# CON_SD_KSDC012551.net
KiCad netlist of a schematic drawn in Altium Designer
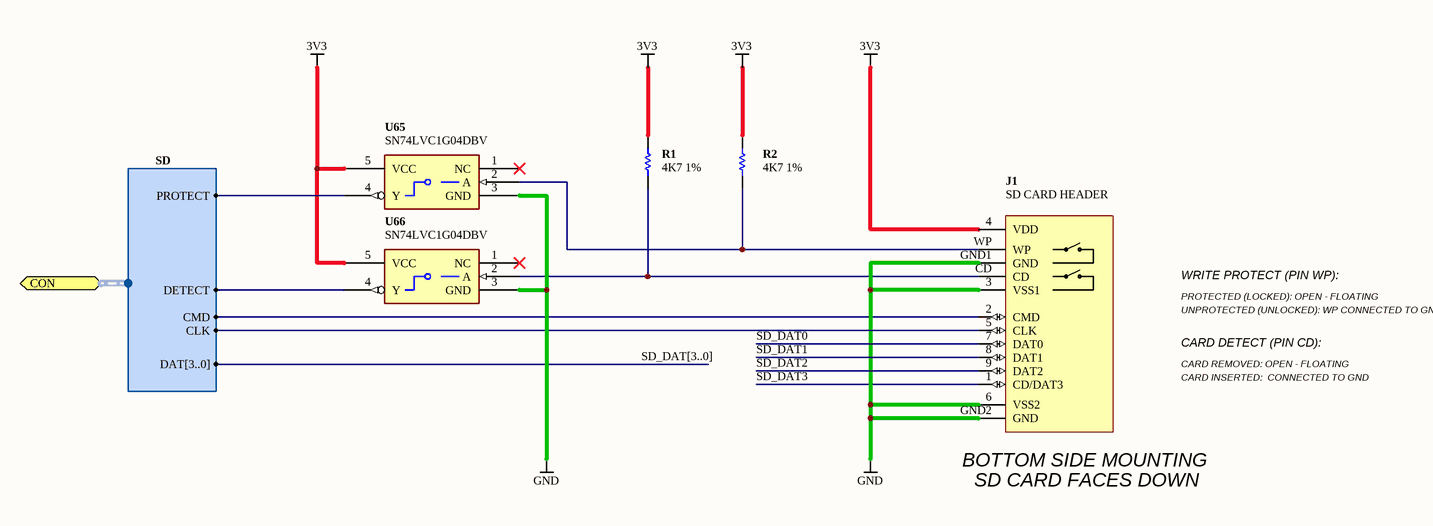
[diagram p0: CON_SD_KSDC012551.SchDoc]

(export (version "E")
  (design (tool "Eeschema 10.0.6"))
  (components
    (comp (ref "J1")
      (value "SD CARD HEADER")
      (footprint "KSDC012551")
      (description "Secure Digital Card Socket")
      (libsource (lib "AltiumDesignLibrary") (part "KSDC012551-9"))
    )
    (comp (ref "R1")
      (value "4K7 1%")
      (footprint "RESC1005-STAR")
      (description "Resistor, 4K7 1% 0402 (1005)")
      (fields (field (name "TOLERANCE") "1 %"))
      (libsource (lib "altium-import") (part "root_0_RES_"))
    )
    (comp (ref "R2")
      (value "4K7 1%")
      (footprint "RESC1005-STAR")
      (description "Resistor, 4K7 1% 0402 (1005)")
      (fields (field (name "TOLERANCE") "1 %"))
      (libsource (lib "altium-import") (part "root_0_RES_"))
    )
    (comp (ref "U65")
      (value "SN74LVC1G04DBV")
      (footprint "SOT95P280-5")
      (description "SN74LVC1G04DBV, Single Inverter Gate, 1.65-V to 5.5-V")
      (libsource (lib "AltiumDesignLibrary") (part "SN74LVC1G04DBV"))
    )
    (comp (ref "U66")
      (value "SN74LVC1G04DBV")
      (footprint "SOT95P280-5")
      (description "SN74LVC1G04DBV, Single Inverter Gate, 1.65-V to 5.5-V")
      (libsource (lib "AltiumDesignLibrary") (part "SN74LVC1G04DBV"))
    )
  )
  (nets
    (net (code "2") (name "/CLK") (class "Default")
      (node (ref "J1") (pin "5") (pinfunction "CLK_5") (pintype "bidirectional"))
    )
    (net (code "3") (name "/CMD") (class "Default")
      (node (ref "J1") (pin "2") (pinfunction "CMD_2") (pintype "bidirectional"))
    )
    (net (code "5") (name "/DETECT") (class "Default")
      (node (ref "U66") (pin "4") (pinfunction "Y_4") (pintype "output"))
    )
    (net (code "6") (name "/PROTECT") (class "Default")
      (node (ref "U65") (pin "4") (pinfunction "Y_4") (pintype "output"))
    )
    (net (code "7") (name "/SD_DAT0") (class "Default")
      (node (ref "J1") (pin "7") (pinfunction "DAT0_7") (pintype "bidirectional"))
    )
    (net (code "8") (name "/SD_DAT1") (class "Default")
      (node (ref "J1") (pin "8") (pinfunction "DAT1_8") (pintype "bidirectional"))
    )
    (net (code "9") (name "/SD_DAT2") (class "Default")
      (node (ref "J1") (pin "9") (pinfunction "DAT2_9") (pintype "bidirectional"))
    )
    (net (code "10") (name "/SD_DAT3") (class "Default")
      (node (ref "J1") (pin "1") (pinfunction "CD/DAT3_1") (pintype "bidirectional"))
    )
    (net (code "12") (name "3V3") (class "Default")
      (node (ref "J1") (pin "4") (pinfunction "VDD_4") (pintype "power_in"))
      (node (ref "R1") (pin "1") (pinfunction "1_1") (pintype "passive"))
      (node (ref "R2") (pin "1") (pinfunction "1_1") (pintype "passive"))
      (node (ref "U65") (pin "5") (pinfunction "VCC_5") (pintype "power_in"))
      (node (ref "U66") (pin "5") (pinfunction "VCC_5") (pintype "power_in"))
    )
    (net (code "13") (name "GND") (class "Default")
      (node (ref "J1") (pin "3") (pinfunction "VSS1_3") (pintype "power_in"))
      (node (ref "J1") (pin "6") (pinfunction "VSS2_6") (pintype "power_in"))
      (node (ref "J1") (pin "GND1") (pinfunction "GND_GND1") (pintype "power_in"))
      (node (ref "J1") (pin "GND2") (pinfunction "GND_GND2") (pintype "power_in"))
      (node (ref "U65") (pin "3") (pinfunction "GND_3") (pintype "power_in"))
      (node (ref "U66") (pin "3") (pinfunction "GND_3") (pintype "power_in"))
    )
    (net (code "14") (name "Net-(U65-A)") (class "Default")
      (node (ref "J1") (pin "WP") (pinfunction "WP_WP") (pintype "open_collector"))
      (node (ref "R2") (pin "2") (pinfunction "2_2") (pintype "passive"))
      (node (ref "U65") (pin "2") (pinfunction "A_2") (pintype "input"))
    )
    (net (code "15") (name "Net-(U66-A)") (class "Default")
      (node (ref "J1") (pin "CD") (pinfunction "CD_CD") (pintype "open_collector"))
      (node (ref "R1") (pin "2") (pinfunction "2_2") (pintype "passive"))
      (node (ref "U66") (pin "2") (pinfunction "A_2") (pintype "input"))
    )
    (net (code "16") (name "unconnected-(U65-NC-Pad1)") (class "Default")
      (node (ref "U65") (pin "1") (pinfunction "NC_1") (pintype "passive+no_connect"))
    )
    (net (code "17") (name "unconnected-(U66-NC-Pad1)") (class "Default")
      (node (ref "U66") (pin "1") (pinfunction "NC_1") (pintype "passive+no_connect"))
    )
  )
)
